# IMX6DL_control.net
KiCad netlist of a schematic drawn in Altium Designer
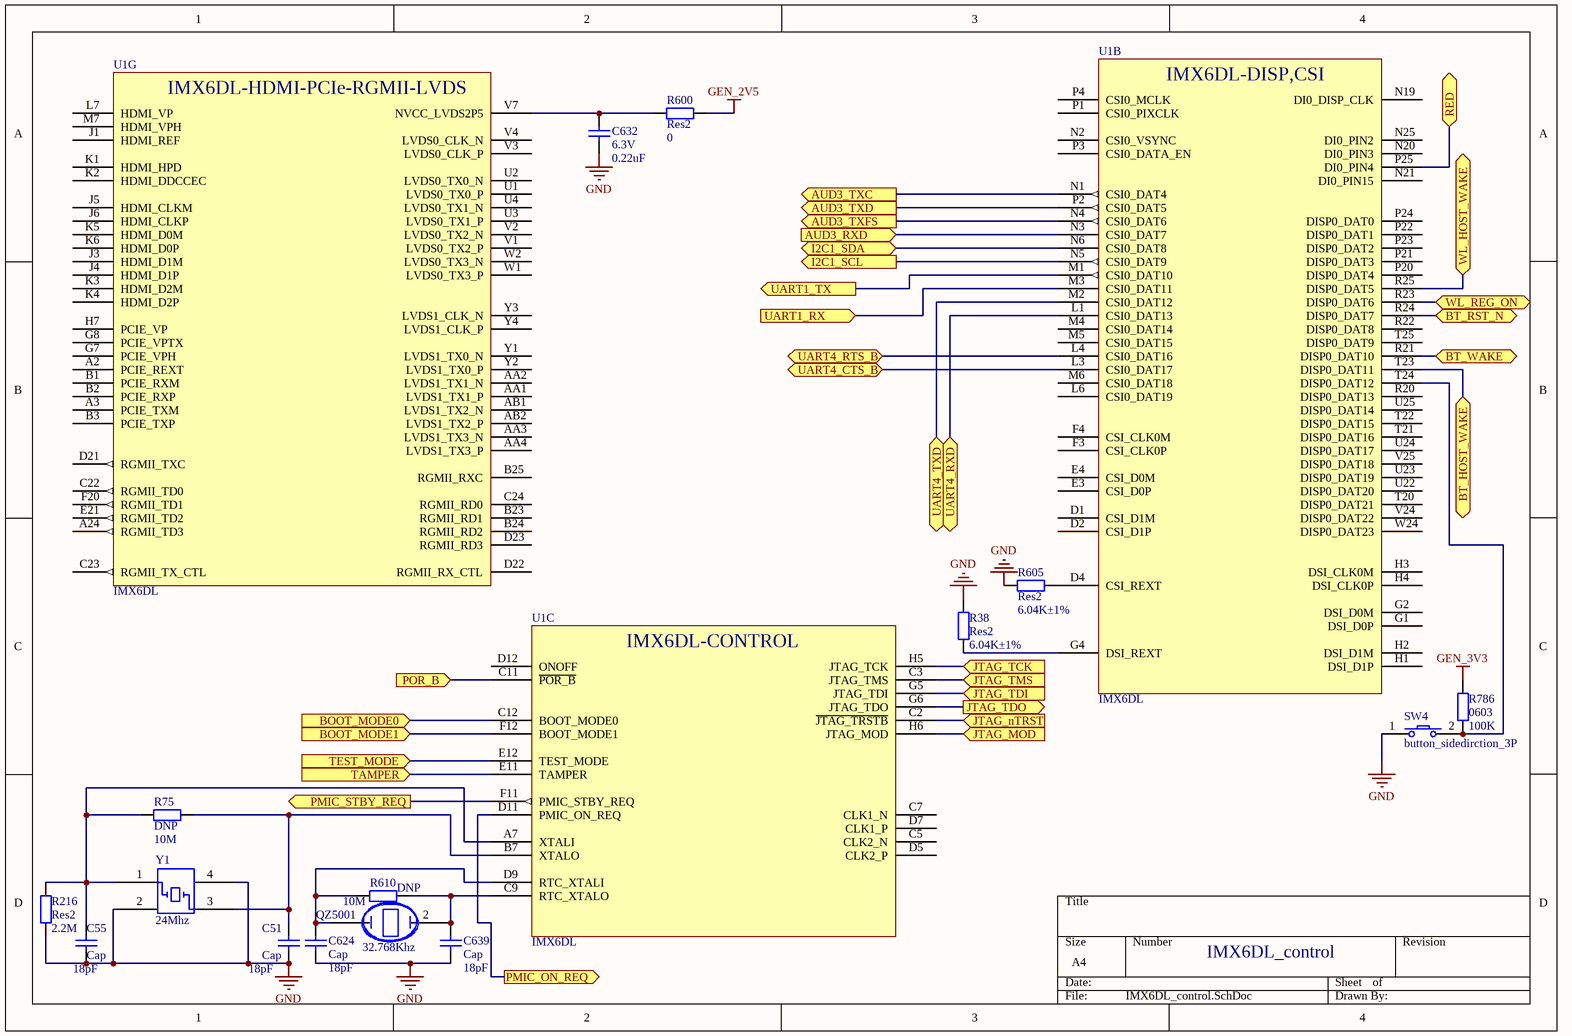
[diagram p0: IMX6DL_control.SchDoc]

(export (version "E")
  (design (tool "Eeschema 10.0.6"))
  (components
    (comp (ref "C51")
      (value "Cap")
      (footprint "0402")
      (description "Capacitor")
      (fields (field (name "ALTIUM_VALUE") "18pF") (field (name "PUBLISHER") "Altium Limited"))
      (libsource (lib "Miscellaneous Devices") (part "Cap"))
    )
    (comp (ref "C55")
      (value "Cap")
      (footprint "0402")
      (description "Capacitor")
      (fields (field (name "ALTIUM_VALUE") "18pF") (field (name "PUBLISHER") "Altium Limited"))
      (libsource (lib "Miscellaneous Devices") (part "Cap"))
    )
    (comp (ref "C624")
      (value "Cap")
      (footprint "0402")
      (description "Capacitor")
      (fields (field (name "ALTIUM_VALUE") "18pF") (field (name "PUBLISHER") "Altium Limited"))
      (libsource (lib "Miscellaneous Devices") (part "Cap"))
    )
    (comp (ref "C632")
      (value "6.3V")
      (footprint "0201")
      (description "Capacitor")
      (fields (field (name "ALTIUM_VALUE") "0.22uF") (field (name "PUBLISHER") "Altium Limited"))
      (libsource (lib "Miscellaneous Devices") (part "Cap"))
    )
    (comp (ref "C639")
      (value "Cap")
      (footprint "0402")
      (description "Capacitor")
      (fields (field (name "ALTIUM_VALUE") "18pF") (field (name "PUBLISHER") "Altium Limited"))
      (libsource (lib "Miscellaneous Devices") (part "Cap"))
    )
    (comp (ref "QZ500")
      (value "32.768Khz")
      (footprint "XTAL32.768Khz-SMT")
      (libsource (lib "IMX6DL") (part "XTAL-32.768KHZ"))
    )
    (comp (ref "R38")
      (value "Res2")
      (footprint "0402")
      (description "Resistor")
      (fields (field (name "ALTIUM_VALUE") "6.04K±1%") (field (name "PUBLISHER") "Altium Limited"))
      (libsource (lib "Miscellaneous Devices") (part "Res2"))
    )
    (comp (ref "R75")
      (value "DNP")
      (footprint "0402")
      (description "Resistor")
      (fields (field (name "ALTIUM_VALUE") "10M") (field (name "PUBLISHER") "Altium Limited"))
      (libsource (lib "") (part "Res2_1"))
    )
    (comp (ref "R216")
      (value "Res2")
      (footprint "0402")
      (description "Resistor")
      (fields (field (name "ALTIUM_VALUE") "2.2M") (field (name "PUBLISHER") "Altium Limited"))
      (libsource (lib "Miscellaneous Devices") (part "Res2"))
    )
    (comp (ref "R600")
      (value "Res2")
      (footprint "0402")
      (description "Resistor")
      (fields (field (name "ALTIUM_VALUE") "0") (field (name "PUBLISHER") "Altium Limited"))
      (libsource (lib "") (part "Res2_1"))
    )
    (comp (ref "R605")
      (value "Res2")
      (footprint "0402")
      (description "Resistor")
      (fields (field (name "ALTIUM_VALUE") "6.04K±1%") (field (name "PUBLISHER") "Altium Limited"))
      (libsource (lib "") (part "Res2_1"))
    )
    (comp (ref "R610")
      (value "DNP")
      (footprint "0402")
      (description "Resistor")
      (fields (field (name "ALTIUM_VALUE") "10M") (field (name "PUBLISHER") "Altium Limited"))
      (libsource (lib "") (part "Res2_1"))
    )
    (comp (ref "R786")
      (value "0603")
      (footprint "0603")
      (description "Resistor")
      (fields (field (name "ALTIUM_VALUE") "100K") (field (name "PUBLISHER") "Altium Limited"))
      (libsource (lib "Miscellaneous Devices") (part "Res2"))
    )
    (comp (ref "SW4")
      (value "button_sidedirction_3P")
      (footprint "button_sidedirction_3P 4.5X4.5")
      (libsource (lib "IMX6DL") (part "button_sidedirction_3P"))
    )
    (comp (ref "U1")
      (value "IMX6DL")
      (footprint "IMX6DL-BGA624x25")
      (libsource (lib "IMX6DL") (part "IMX6DL"))
    )
    (comp (ref "Y1")
      (value "24Mhz")
      (footprint "XTL571300LLI24.000-10TR")
      (libsource (lib "IMX6DL") (part "XTAL"))
    )
  )
  (nets
    (net (code "1") (name "/AUD3_RXD") (class "Default")
      (node (ref "U1") (pin "N3") (pinfunction "CSI0_DAT7_N3") (pintype "passive"))
    )
    (net (code "2") (name "/AUD3_TXC") (class "Default")
      (node (ref "U1") (pin "N1") (pinfunction "CSI0_DAT4_N1") (pintype "passive"))
    )
    (net (code "3") (name "/AUD3_TXD") (class "Default")
      (node (ref "U1") (pin "P2") (pinfunction "CSI0_DAT5_P2") (pintype "passive"))
    )
    (net (code "4") (name "/AUD3_TXFS") (class "Default")
      (node (ref "U1") (pin "N4") (pinfunction "CSI0_DAT6_N4") (pintype "passive"))
    )
    (net (code "5") (name "/BOOT_MODE0") (class "Default")
      (node (ref "U1") (pin "C12") (pinfunction "BOOT_MODE0_C12") (pintype "passive"))
    )
    (net (code "6") (name "/BOOT_MODE1") (class "Default")
      (node (ref "U1") (pin "F12") (pinfunction "BOOT_MODE1_F12") (pintype "passive"))
    )
    (net (code "7") (name "/BT_HOST_WAKE") (class "Default")
      (node (ref "U1") (pin "T23") (pinfunction "DISP0_DAT11_T23") (pintype "passive"))
    )
    (net (code "8") (name "/BT_RST_N") (class "Default")
      (node (ref "U1") (pin "R24") (pinfunction "DISP0_DAT7_R24") (pintype "passive"))
    )
    (net (code "9") (name "/BT_WAKE") (class "Default")
      (node (ref "U1") (pin "R21") (pinfunction "DISP0_DAT10_R21") (pintype "passive"))
    )
    (net (code "10") (name "/I2C1_SCL") (class "Default")
      (node (ref "U1") (pin "N5") (pinfunction "CSI0_DAT9_N5") (pintype "passive"))
    )
    (net (code "11") (name "/I2C1_SDA") (class "Default")
      (node (ref "U1") (pin "N6") (pinfunction "CSI0_DAT8_N6") (pintype "passive"))
    )
    (net (code "12") (name "/JTAG_MOD") (class "Default")
      (node (ref "U1") (pin "H6") (pinfunction "JTAG_MOD_H6") (pintype "passive"))
    )
    (net (code "13") (name "/JTAG_TCK") (class "Default")
      (node (ref "U1") (pin "H5") (pinfunction "JTAG_TCK_H5") (pintype "passive"))
    )
    (net (code "14") (name "/JTAG_TDI") (class "Default")
      (node (ref "U1") (pin "G5") (pinfunction "JTAG_TDI_G5") (pintype "passive"))
    )
    (net (code "15") (name "/JTAG_TDO") (class "Default")
      (node (ref "U1") (pin "G6") (pinfunction "JTAG_TDO_G6") (pintype "passive"))
    )
    (net (code "16") (name "/JTAG_TMS") (class "Default")
      (node (ref "U1") (pin "C3") (pinfunction "JTAG_TMS_C3") (pintype "passive"))
    )
    (net (code "17") (name "/JTAG_nTRST") (class "Default")
      (node (ref "U1") (pin "C2") (pinfunction "~{JTAG_TRSTB}_C2") (pintype "passive"))
    )
    (net (code "18") (name "/PMIC_ON_REQ") (class "Default")
      (node (ref "U1") (pin "D11") (pinfunction "PMIC_ON_REQ_D11") (pintype "passive"))
    )
    (net (code "19") (name "/PMIC_STBY_REQ") (class "Default")
      (node (ref "U1") (pin "F11") (pinfunction "PMIC_STBY_REQ_F11") (pintype "passive"))
    )
    (net (code "20") (name "/POR_B") (class "Default")
      (node (ref "U1") (pin "C11") (pinfunction "~{POR_B}_C11") (pintype "passive"))
    )
    (net (code "21") (name "/RED") (class "Default")
      (node (ref "U1") (pin "P25") (pinfunction "DI0_PIN4_P25") (pintype "passive"))
    )
    (net (code "22") (name "/TAMPER") (class "Default")
      (node (ref "U1") (pin "E11") (pinfunction "TAMPER_E11") (pintype "passive"))
    )
    (net (code "23") (name "/TEST_MODE") (class "Default")
      (node (ref "U1") (pin "E12") (pinfunction "TEST_MODE_E12") (pintype "passive"))
    )
    (net (code "24") (name "/UART1_RX") (class "Default")
      (node (ref "U1") (pin "M3") (pinfunction "CSI0_DAT11_M3") (pintype "passive"))
    )
    (net (code "25") (name "/UART1_TX") (class "Default")
      (node (ref "U1") (pin "M1") (pinfunction "CSI0_DAT10_M1") (pintype "passive"))
    )
    (net (code "26") (name "/UART4_CTS_B") (class "Default")
      (node (ref "U1") (pin "L3") (pinfunction "CSI0_DAT17_L3") (pintype "passive"))
    )
    (net (code "27") (name "/UART4_RTS_B") (class "Default")
      (node (ref "U1") (pin "L4") (pinfunction "CSI0_DAT16_L4") (pintype "passive"))
    )
    (net (code "28") (name "/UART4_RXD") (class "Default")
      (node (ref "U1") (pin "L1") (pinfunction "CSI0_DAT13_L1") (pintype "passive"))
    )
    (net (code "29") (name "/UART4_TXD") (class "Default")
      (node (ref "U1") (pin "M2") (pinfunction "CSI0_DAT12_M2") (pintype "passive"))
    )
    (net (code "30") (name "/WL_HOST_WAKE") (class "Default")
      (node (ref "U1") (pin "R25") (pinfunction "DISP0_DAT5_R25") (pintype "passive"))
    )
    (net (code "31") (name "/WL_REG_ON") (class "Default")
      (node (ref "U1") (pin "R23") (pinfunction "DISP0_DAT6_R23") (pintype "passive"))
    )
    (net (code "32") (name "GEN_2V5") (class "Default")
      (node (ref "R600") (pin "2") (pinfunction "2_2") (pintype "passive"))
    )
    (net (code "33") (name "GEN_3V3") (class "Default")
      (node (ref "R786") (pin "2") (pinfunction "2_2") (pintype "passive"))
    )
    (net (code "34") (name "GND") (class "Default")
      (node (ref "C51") (pin "1") (pinfunction "1_1") (pintype "passive"))
      (node (ref "C55") (pin "1") (pinfunction "1_1") (pintype "passive"))
      (node (ref "C624") (pin "1") (pinfunction "1_1") (pintype "passive"))
      (node (ref "C632") (pin "1") (pinfunction "1_1") (pintype "passive"))
      (node (ref "C639") (pin "1") (pinfunction "1_1") (pintype "passive"))
      (node (ref "R216") (pin "1") (pinfunction "1_1") (pintype "passive"))
      (node (ref "R38") (pin "2") (pinfunction "2_2") (pintype "passive"))
      (node (ref "R605") (pin "1") (pinfunction "1_1") (pintype "passive"))
      (node (ref "SW4") (pin "1") (pinfunction "3_1") (pintype "passive"))
      (node (ref "Y1") (pin "2") (pinfunction "58_2") (pintype "passive"))
      (node (ref "Y1") (pin "4") (pinfunction "60_4") (pintype "passive"))
    )
    (net (code "35") (name "Net-(U1B-CSI_REXT)") (class "Default")
      (node (ref "R605") (pin "2") (pinfunction "2_2") (pintype "passive"))
      (node (ref "U1") (pin "D4") (pinfunction "CSI_REXT_D4") (pintype "passive"))
    )
    (net (code "36") (name "Net-(U1B-DISP0_DAT12)") (class "Default")
      (node (ref "R786") (pin "1") (pinfunction "1_1") (pintype "passive"))
      (node (ref "SW4") (pin "2") (pinfunction "2_2") (pintype "passive"))
      (node (ref "U1") (pin "T24") (pinfunction "DISP0_DAT12_T24") (pintype "passive"))
    )
    (net (code "37") (name "Net-(U1B-DSI_REXT)") (class "Default")
      (node (ref "R38") (pin "1") (pinfunction "1_1") (pintype "passive"))
      (node (ref "U1") (pin "G4") (pinfunction "DSI_REXT_G4") (pintype "passive"))
    )
    (net (code "38") (name "Net-(U1C-RTC_XTALI)") (class "Default")
      (node (ref "C624") (pin "2") (pinfunction "2_2") (pintype "passive"))
      (node (ref "QZ500") (pin "1") (pinfunction "1_1") (pintype "passive"))
      (node (ref "R610") (pin "1") (pinfunction "1_1") (pintype "passive"))
      (node (ref "U1") (pin "D9") (pinfunction "RTC_XTALI_D9") (pintype "passive"))
    )
    (net (code "39") (name "Net-(U1C-RTC_XTALO)") (class "Default")
      (node (ref "C639") (pin "2") (pinfunction "2_2") (pintype "passive"))
      (node (ref "QZ500") (pin "2") (pinfunction "2_2") (pintype "passive"))
      (node (ref "R610") (pin "2") (pinfunction "2_2") (pintype "passive"))
      (node (ref "U1") (pin "C9") (pinfunction "RTC_XTALO_C9") (pintype "passive"))
    )
    (net (code "40") (name "Net-(U1C-XTALI)") (class "Default")
      (node (ref "C55") (pin "2") (pinfunction "2_2") (pintype "passive"))
      (node (ref "R216") (pin "2") (pinfunction "2_2") (pintype "passive"))
      (node (ref "R75") (pin "1") (pinfunction "1_1") (pintype "passive"))
      (node (ref "U1") (pin "A7") (pinfunction "XTALI_A7") (pintype "passive"))
      (node (ref "Y1") (pin "1") (pinfunction "57_1") (pintype "passive"))
    )
    (net (code "41") (name "Net-(U1C-XTALO)") (class "Default")
      (node (ref "C51") (pin "2") (pinfunction "2_2") (pintype "passive"))
      (node (ref "R75") (pin "2") (pinfunction "2_2") (pintype "passive"))
      (node (ref "U1") (pin "B7") (pinfunction "XTALO_B7") (pintype "passive"))
      (node (ref "Y1") (pin "3") (pinfunction "59_3") (pintype "passive"))
    )
    (net (code "42") (name "Net-(U1G-NVCC_LVDS2P5)") (class "Default")
      (node (ref "C632") (pin "2") (pinfunction "2_2") (pintype "passive"))
      (node (ref "R600") (pin "1") (pinfunction "1_1") (pintype "passive"))
      (node (ref "U1") (pin "V7") (pinfunction "NVCC_LVDS2P5_V7") (pintype "passive"))
    )
    (net (code "43") (name "unconnected-(U1B-CSI0_DAT14-PadM4)") (class "Default")
      (node (ref "U1") (pin "M4") (pinfunction "CSI0_DAT14_M4") (pintype "passive"))
    )
    (net (code "44") (name "unconnected-(U1B-CSI0_DAT15-PadM5)") (class "Default")
      (node (ref "U1") (pin "M5") (pinfunction "CSI0_DAT15_M5") (pintype "passive"))
    )
    (net (code "45") (name "unconnected-(U1B-CSI0_DAT18-PadM6)") (class "Default")
      (node (ref "U1") (pin "M6") (pinfunction "CSI0_DAT18_M6") (pintype "passive"))
    )
    (net (code "46") (name "unconnected-(U1B-CSI0_DAT19-PadL6)") (class "Default")
      (node (ref "U1") (pin "L6") (pinfunction "CSI0_DAT19_L6") (pintype "passive"))
    )
    (net (code "47") (name "unconnected-(U1B-CSI0_DATA_EN-PadP3)") (class "Default")
      (node (ref "U1") (pin "P3") (pinfunction "CSI0_DATA_EN_P3") (pintype "passive"))
    )
    (net (code "48") (name "unconnected-(U1B-CSI0_MCLK-PadP4)") (class "Default")
      (node (ref "U1") (pin "P4") (pinfunction "CSI0_MCLK_P4") (pintype "passive"))
    )
    (net (code "49") (name "unconnected-(U1B-CSI0_PIXCLK-PadP1)") (class "Default")
      (node (ref "U1") (pin "P1") (pinfunction "CSI0_PIXCLK_P1") (pintype "passive"))
    )
    (net (code "50") (name "unconnected-(U1B-CSI0_VSYNC-PadN2)") (class "Default")
      (node (ref "U1") (pin "N2") (pinfunction "CSI0_VSYNC_N2") (pintype "passive"))
    )
    (net (code "51") (name "unconnected-(U1B-CSI_CLK0M-PadF4)") (class "Default")
      (node (ref "U1") (pin "F4") (pinfunction "CSI_CLK0M_F4") (pintype "passive"))
    )
    (net (code "52") (name "unconnected-(U1B-CSI_CLK0P-PadF3)") (class "Default")
      (node (ref "U1") (pin "F3") (pinfunction "CSI_CLK0P_F3") (pintype "passive"))
    )
    (net (code "53") (name "unconnected-(U1B-CSI_D0M-PadE4)") (class "Default")
      (node (ref "U1") (pin "E4") (pinfunction "CSI_D0M_E4") (pintype "passive"))
    )
    (net (code "54") (name "unconnected-(U1B-CSI_D0P-PadE3)") (class "Default")
      (node (ref "U1") (pin "E3") (pinfunction "CSI_D0P_E3") (pintype "passive"))
    )
    (net (code "55") (name "unconnected-(U1B-CSI_D1M-PadD1)") (class "Default")
      (node (ref "U1") (pin "D1") (pinfunction "CSI_D1M_D1") (pintype "passive"))
    )
    (net (code "56") (name "unconnected-(U1B-CSI_D1P-PadD2)") (class "Default")
      (node (ref "U1") (pin "D2") (pinfunction "CSI_D1P_D2") (pintype "passive"))
    )
    (net (code "57") (name "unconnected-(U1B-DI0_DISP_CLK-PadN19)") (class "Default")
      (node (ref "U1") (pin "N19") (pinfunction "DI0_DISP_CLK_N19") (pintype "passive"))
    )
    (net (code "58") (name "unconnected-(U1B-DI0_PIN2-PadN25)") (class "Default")
      (node (ref "U1") (pin "N25") (pinfunction "DI0_PIN2_N25") (pintype "passive"))
    )
    (net (code "59") (name "unconnected-(U1B-DI0_PIN3-PadN20)") (class "Default")
      (node (ref "U1") (pin "N20") (pinfunction "DI0_PIN3_N20") (pintype "passive"))
    )
    (net (code "60") (name "unconnected-(U1B-DI0_PIN15-PadN21)") (class "Default")
      (node (ref "U1") (pin "N21") (pinfunction "DI0_PIN15_N21") (pintype "passive"))
    )
    (net (code "61") (name "unconnected-(U1B-DISP0_DAT0-PadP24)") (class "Default")
      (node (ref "U1") (pin "P24") (pinfunction "DISP0_DAT0_P24") (pintype "passive"))
    )
    (net (code "62") (name "unconnected-(U1B-DISP0_DAT1-PadP22)") (class "Default")
      (node (ref "U1") (pin "P22") (pinfunction "DISP0_DAT1_P22") (pintype "passive"))
    )
    (net (code "63") (name "unconnected-(U1B-DISP0_DAT2-PadP23)") (class "Default")
      (node (ref "U1") (pin "P23") (pinfunction "DISP0_DAT2_P23") (pintype "passive"))
    )
    (net (code "64") (name "unconnected-(U1B-DISP0_DAT3-PadP21)") (class "Default")
      (node (ref "U1") (pin "P21") (pinfunction "DISP0_DAT3_P21") (pintype "passive"))
    )
    (net (code "65") (name "unconnected-(U1B-DISP0_DAT4-PadP20)") (class "Default")
      (node (ref "U1") (pin "P20") (pinfunction "DISP0_DAT4_P20") (pintype "passive"))
    )
    (net (code "66") (name "unconnected-(U1B-DISP0_DAT8-PadR22)") (class "Default")
      (node (ref "U1") (pin "R22") (pinfunction "DISP0_DAT8_R22") (pintype "passive"))
    )
    (net (code "67") (name "unconnected-(U1B-DISP0_DAT9-PadT25)") (class "Default")
      (node (ref "U1") (pin "T25") (pinfunction "DISP0_DAT9_T25") (pintype "passive"))
    )
    (net (code "68") (name "unconnected-(U1B-DISP0_DAT13-PadR20)") (class "Default")
      (node (ref "U1") (pin "R20") (pinfunction "DISP0_DAT13_R20") (pintype "passive"))
    )
    (net (code "69") (name "unconnected-(U1B-DISP0_DAT14-PadU25)") (class "Default")
      (node (ref "U1") (pin "U25") (pinfunction "DISP0_DAT14_U25") (pintype "passive"))
    )
    (net (code "70") (name "unconnected-(U1B-DISP0_DAT15-PadT22)") (class "Default")
      (node (ref "U1") (pin "T22") (pinfunction "DISP0_DAT15_T22") (pintype "passive"))
    )
    (net (code "71") (name "unconnected-(U1B-DISP0_DAT16-PadT21)") (class "Default")
      (node (ref "U1") (pin "T21") (pinfunction "DISP0_DAT16_T21") (pintype "passive"))
    )
    (net (code "72") (name "unconnected-(U1B-DISP0_DAT17-PadU24)") (class "Default")
      (node (ref "U1") (pin "U24") (pinfunction "DISP0_DAT17_U24") (pintype "passive"))
    )
    (net (code "73") (name "unconnected-(U1B-DISP0_DAT18-PadV25)") (class "Default")
      (node (ref "U1") (pin "V25") (pinfunction "DISP0_DAT18_V25") (pintype "passive"))
    )
    (net (code "74") (name "unconnected-(U1B-DISP0_DAT19-PadU23)") (class "Default")
      (node (ref "U1") (pin "U23") (pinfunction "DISP0_DAT19_U23") (pintype "passive"))
    )
    (net (code "75") (name "unconnected-(U1B-DISP0_DAT20-PadU22)") (class "Default")
      (node (ref "U1") (pin "U22") (pinfunction "DISP0_DAT20_U22") (pintype "passive"))
    )
    (net (code "76") (name "unconnected-(U1B-DISP0_DAT21-PadT20)") (class "Default")
      (node (ref "U1") (pin "T20") (pinfunction "DISP0_DAT21_T20") (pintype "passive"))
    )
    (net (code "77") (name "unconnected-(U1B-DISP0_DAT22-PadV24)") (class "Default")
      (node (ref "U1") (pin "V24") (pinfunction "DISP0_DAT22_V24") (pintype "passive"))
    )
    (net (code "78") (name "unconnected-(U1B-DISP0_DAT23-PadW24)") (class "Default")
      (node (ref "U1") (pin "W24") (pinfunction "DISP0_DAT23_W24") (pintype "passive"))
    )
    (net (code "79") (name "unconnected-(U1B-DSI_CLK0M-PadH3)") (class "Default")
      (node (ref "U1") (pin "H3") (pinfunction "DSI_CLK0M_H3") (pintype "passive"))
    )
    (net (code "80") (name "unconnected-(U1B-DSI_CLK0P-PadH4)") (class "Default")
      (node (ref "U1") (pin "H4") (pinfunction "DSI_CLK0P_H4") (pintype "passive"))
    )
    (net (code "81") (name "unconnected-(U1B-DSI_D0M-PadG2)") (class "Default")
      (node (ref "U1") (pin "G2") (pinfunction "DSI_D0M_G2") (pintype "passive"))
    )
    (net (code "82") (name "unconnected-(U1B-DSI_D0P-PadG1)") (class "Default")
      (node (ref "U1") (pin "G1") (pinfunction "DSI_D0P_G1") (pintype "passive"))
    )
    (net (code "83") (name "unconnected-(U1B-DSI_D1M-PadH2)") (class "Default")
      (node (ref "U1") (pin "H2") (pinfunction "DSI_D1M_H2") (pintype "passive"))
    )
    (net (code "84") (name "unconnected-(U1B-DSI_D1P-PadH1)") (class "Default")
      (node (ref "U1") (pin "H1") (pinfunction "DSI_D1P_H1") (pintype "passive"))
    )
    (net (code "85") (name "unconnected-(U1C-CLK1_N-PadC7)") (class "Default")
      (node (ref "U1") (pin "C7") (pinfunction "CLK1_N_C7") (pintype "passive"))
    )
    (net (code "86") (name "unconnected-(U1C-CLK1_P-PadD7)") (class "Default")
      (node (ref "U1") (pin "D7") (pinfunction "CLK1_P_D7") (pintype "passive"))
    )
    (net (code "87") (name "unconnected-(U1C-CLK2_N-PadC5)") (class "Default")
      (node (ref "U1") (pin "C5") (pinfunction "CLK2_N_C5") (pintype "passive"))
    )
    (net (code "88") (name "unconnected-(U1C-CLK2_P-PadD5)") (class "Default")
      (node (ref "U1") (pin "D5") (pinfunction "CLK2_P_D5") (pintype "passive"))
    )
    (net (code "89") (name "unconnected-(U1C-ONOFF-PadD12)") (class "Default")
      (node (ref "U1") (pin "D12") (pinfunction "ONOFF_D12") (pintype "passive"))
    )
    (net (code "90") (name "unconnected-(U1G-HDMI_CLKM-PadJ5)") (class "Default")
      (node (ref "U1") (pin "J5") (pinfunction "HDMI_CLKM_J5") (pintype "passive"))
    )
    (net (code "91") (name "unconnected-(U1G-HDMI_CLKP-PadJ6)") (class "Default")
      (node (ref "U1") (pin "J6") (pinfunction "HDMI_CLKP_J6") (pintype "passive"))
    )
    (net (code "92") (name "unconnected-(U1G-HDMI_D0M-PadK5)") (class "Default")
      (node (ref "U1") (pin "K5") (pinfunction "HDMI_D0M_K5") (pintype "passive"))
    )
    (net (code "93") (name "unconnected-(U1G-HDMI_D0P-PadK6)") (class "Default")
      (node (ref "U1") (pin "K6") (pinfunction "HDMI_D0P_K6") (pintype "passive"))
    )
    (net (code "94") (name "unconnected-(U1G-HDMI_D1M-PadJ3)") (class "Default")
      (node (ref "U1") (pin "J3") (pinfunction "HDMI_D1M_J3") (pintype "passive"))
    )
    (net (code "95") (name "unconnected-(U1G-HDMI_D1P-PadJ4)") (class "Default")
      (node (ref "U1") (pin "J4") (pinfunction "HDMI_D1P_J4") (pintype "passive"))
    )
    (net (code "96") (name "unconnected-(U1G-HDMI_D2M-PadK3)") (class "Default")
      (node (ref "U1") (pin "K3") (pinfunction "HDMI_D2M_K3") (pintype "passive"))
    )
    (net (code "97") (name "unconnected-(U1G-HDMI_D2P-PadK4)") (class "Default")
      (node (ref "U1") (pin "K4") (pinfunction "HDMI_D2P_K4") (pintype "passive"))
    )
    (net (code "98") (name "unconnected-(U1G-HDMI_DDCCEC-PadK2)") (class "Default")
      (node (ref "U1") (pin "K2") (pinfunction "HDMI_DDCCEC_K2") (pintype "passive"))
    )
    (net (code "99") (name "unconnected-(U1G-HDMI_HPD-PadK1)") (class "Default")
      (node (ref "U1") (pin "K1") (pinfunction "HDMI_HPD_K1") (pintype "passive"))
    )
    (net (code "100") (name "unconnected-(U1G-HDMI_REF-PadJ1)") (class "Default")
      (node (ref "U1") (pin "J1") (pinfunction "HDMI_REF_J1") (pintype "passive"))
    )
    (net (code "101") (name "unconnected-(U1G-HDMI_VP-PadL7)") (class "Default")
      (node (ref "U1") (pin "L7") (pinfunction "HDMI_VP_L7") (pintype "passive"))
    )
    (net (code "102") (name "unconnected-(U1G-HDMI_VPH-PadM7)") (class "Default")
      (node (ref "U1") (pin "M7") (pinfunction "HDMI_VPH_M7") (pintype "passive"))
    )
    (net (code "103") (name "unconnected-(U1G-LVDS0_CLK_N-PadV4)") (class "Default")
      (node (ref "U1") (pin "V4") (pinfunction "LVDS0_CLK_N_V4") (pintype "passive"))
    )
    (net (code "104") (name "unconnected-(U1G-LVDS0_CLK_P-PadV3)") (class "Default")
      (node (ref "U1") (pin "V3") (pinfunction "LVDS0_CLK_P_V3") (pintype "passive"))
    )
    (net (code "105") (name "unconnected-(U1G-LVDS0_TX0_N-PadU2)") (class "Default")
      (node (ref "U1") (pin "U2") (pinfunction "LVDS0_TX0_N_U2") (pintype "passive"))
    )
    (net (code "106") (name "unconnected-(U1G-LVDS0_TX0_P-PadU1)") (class "Default")
      (node (ref "U1") (pin "U1") (pinfunction "LVDS0_TX0_P_U1") (pintype "passive"))
    )
    (net (code "107") (name "unconnected-(U1G-LVDS0_TX1_N-PadU4)") (class "Default")
      (node (ref "U1") (pin "U4") (pinfunction "LVDS0_TX1_N_U4") (pintype "passive"))
    )
    (net (code "108") (name "unconnected-(U1G-LVDS0_TX1_P-PadU3)") (class "Default")
      (node (ref "U1") (pin "U3") (pinfunction "LVDS0_TX1_P_U3") (pintype "passive"))
    )
    (net (code "109") (name "unconnected-(U1G-LVDS0_TX2_N-PadV2)") (class "Default")
      (node (ref "U1") (pin "V2") (pinfunction "LVDS0_TX2_N_V2") (pintype "passive"))
    )
    (net (code "110") (name "unconnected-(U1G-LVDS0_TX2_P-PadV1)") (class "Default")
      (node (ref "U1") (pin "V1") (pinfunction "LVDS0_TX2_P_V1") (pintype "passive"))
    )
    (net (code "111") (name "unconnected-(U1G-LVDS0_TX3_N-PadW2)") (class "Default")
      (node (ref "U1") (pin "W2") (pinfunction "LVDS0_TX3_N_W2") (pintype "passive"))
    )
    (net (code "112") (name "unconnected-(U1G-LVDS0_TX3_P-PadW1)") (class "Default")
      (node (ref "U1") (pin "W1") (pinfunction "LVDS0_TX3_P_W1") (pintype "passive"))
    )
    (net (code "113") (name "unconnected-(U1G-LVDS1_CLK_N-PadY3)") (class "Default")
      (node (ref "U1") (pin "Y3") (pinfunction "LVDS1_CLK_N_Y3") (pintype "passive"))
    )
    (net (code "114") (name "unconnected-(U1G-LVDS1_CLK_P-PadY4)") (class "Default")
      (node (ref "U1") (pin "Y4") (pinfunction "LVDS1_CLK_P_Y4") (pintype "passive"))
    )
    (net (code "115") (name "unconnected-(U1G-LVDS1_TX0_N-PadY1)") (class "Default")
      (node (ref "U1") (pin "Y1") (pinfunction "LVDS1_TX0_N_Y1") (pintype "passive"))
    )
    (net (code "116") (name "unconnected-(U1G-LVDS1_TX0_P-PadY2)") (class "Default")
      (node (ref "U1") (pin "Y2") (pinfunction "LVDS1_TX0_P_Y2") (pintype "passive"))
    )
    (net (code "117") (name "unconnected-(U1G-LVDS1_TX1_N-PadAA2)") (class "Default")
      (node (ref "U1") (pin "AA2") (pinfunction "LVDS1_TX1_N_AA2") (pintype "passive"))
    )
    (net (code "118") (name "unconnected-(U1G-LVDS1_TX1_P-PadAA1)") (class "Default")
      (node (ref "U1") (pin "AA1") (pinfunction "LVDS1_TX1_P_AA1") (pintype "passive"))
    )
    (net (code "119") (name "unconnected-(U1G-LVDS1_TX2_N-PadAB1)") (class "Default")
      (node (ref "U1") (pin "AB1") (pinfunction "LVDS1_TX2_N_AB1") (pintype "passive"))
    )
    (net (code "120") (name "unconnected-(U1G-LVDS1_TX2_P-PadAB2)") (class "Default")
      (node (ref "U1") (pin "AB2") (pinfunction "LVDS1_TX2_P_AB2") (pintype "passive"))
    )
    (net (code "121") (name "unconnected-(U1G-LVDS1_TX3_N-PadAA3)") (class "Default")
      (node (ref "U1") (pin "AA3") (pinfunction "LVDS1_TX3_N_AA3") (pintype "passive"))
    )
    (net (code "122") (name "unconnected-(U1G-LVDS1_TX3_P-PadAA4)") (class "Default")
      (node (ref "U1") (pin "AA4") (pinfunction "LVDS1_TX3_P_AA4") (pintype "passive"))
    )
    (net (code "123") (name "unconnected-(U1G-PCIE_REXT-PadA2)") (class "Default")
      (node (ref "U1") (pin "A2") (pinfunction "PCIE_REXT_A2") (pintype "passive"))
    )
    (net (code "124") (name "unconnected-(U1G-PCIE_RXM-PadB1)") (class "Default")
      (node (ref "U1") (pin "B1") (pinfunction "PCIE_RXM_B1") (pintype "passive"))
    )
    (net (code "125") (name "unconnected-(U1G-PCIE_RXP-PadB2)") (class "Default")
      (node (ref "U1") (pin "B2") (pinfunction "PCIE_RXP_B2") (pintype "passive"))
    )
    (net (code "126") (name "unconnected-(U1G-PCIE_TXM-PadA3)") (class "Default")
      (node (ref "U1") (pin "A3") (pinfunction "PCIE_TXM_A3") (pintype "passive"))
    )
    (net (code "127") (name "unconnected-(U1G-PCIE_TXP-PadB3)") (class "Default")
      (node (ref "U1") (pin "B3") (pinfunction "PCIE_TXP_B3") (pintype "passive"))
    )
    (net (code "128") (name "unconnected-(U1G-PCIE_VP-PadH7)") (class "Default")
      (node (ref "U1") (pin "H7") (pinfunction "PCIE_VP_H7") (pintype "passive"))
    )
    (net (code "129") (name "unconnected-(U1G-PCIE_VPH-PadG7)") (class "Default")
      (node (ref "U1") (pin "G7") (pinfunction "PCIE_VPH_G7") (pintype "passive"))
    )
    (net (code "130") (name "unconnected-(U1G-PCIE_VPTX-PadG8)") (class "Default")
      (node (ref "U1") (pin "G8") (pinfunction "PCIE_VPTX_G8") (pintype "passive"))
    )
    (net (code "131") (name "unconnected-(U1G-RGMII_RD0-PadC24)") (class "Default")
      (node (ref "U1") (pin "C24") (pinfunction "RGMII_RD0_C24") (pintype "passive"))
    )
    (net (code "132") (name "unconnected-(U1G-RGMII_RD1-PadB23)") (class "Default")
      (node (ref "U1") (pin "B23") (pinfunction "RGMII_RD1_B23") (pintype "passive"))
    )
    (net (code "133") (name "unconnected-(U1G-RGMII_RD2-PadB24)") (class "Default")
      (node (ref "U1") (pin "B24") (pinfunction "RGMII_RD2_B24") (pintype "passive"))
    )
    (net (code "134") (name "unconnected-(U1G-RGMII_RD3-PadD23)") (class "Default")
      (node (ref "U1") (pin "D23") (pinfunction "RGMII_RD3_D23") (pintype "passive"))
    )
    (net (code "135") (name "unconnected-(U1G-RGMII_RXC-PadB25)") (class "Default")
      (node (ref "U1") (pin "B25") (pinfunction "RGMII_RXC_B25") (pintype "passive"))
    )
    (net (code "136") (name "unconnected-(U1G-RGMII_RX_CTL-PadD22)") (class "Default")
      (node (ref "U1") (pin "D22") (pinfunction "RGMII_RX_CTL_D22") (pintype "passive"))
    )
    (net (code "137") (name "unconnected-(U1G-RGMII_TD0-PadC22)") (class "Default")
      (node (ref "U1") (pin "C22") (pinfunction "RGMII_TD0_C22") (pintype "output"))
    )
    (net (code "138") (name "unconnected-(U1G-RGMII_TD1-PadF20)") (class "Default")
      (node (ref "U1") (pin "F20") (pinfunction "RGMII_TD1_F20") (pintype "output"))
    )
    (net (code "139") (name "unconnected-(U1G-RGMII_TD2-PadE21)") (class "Default")
      (node (ref "U1") (pin "E21") (pinfunction "RGMII_TD2_E21") (pintype "output"))
    )
    (net (code "140") (name "unconnected-(U1G-RGMII_TD3-PadA24)") (class "Default")
      (node (ref "U1") (pin "A24") (pinfunction "RGMII_TD3_A24") (pintype "output"))
    )
    (net (code "141") (name "unconnected-(U1G-RGMII_TXC-PadD21)") (class "Default")
      (node (ref "U1") (pin "D21") (pinfunction "RGMII_TXC_D21") (pintype "output"))
    )
    (net (code "142") (name "unconnected-(U1G-RGMII_TX_CTL-PadC23)") (class "Default")
      (node (ref "U1") (pin "C23") (pinfunction "RGMII_TX_CTL_C23") (pintype "output"))
    )
  )
)
